# CAN_BUS_FOR_STM32.net
KiCad netlist of a schematic drawn in Altium Designer
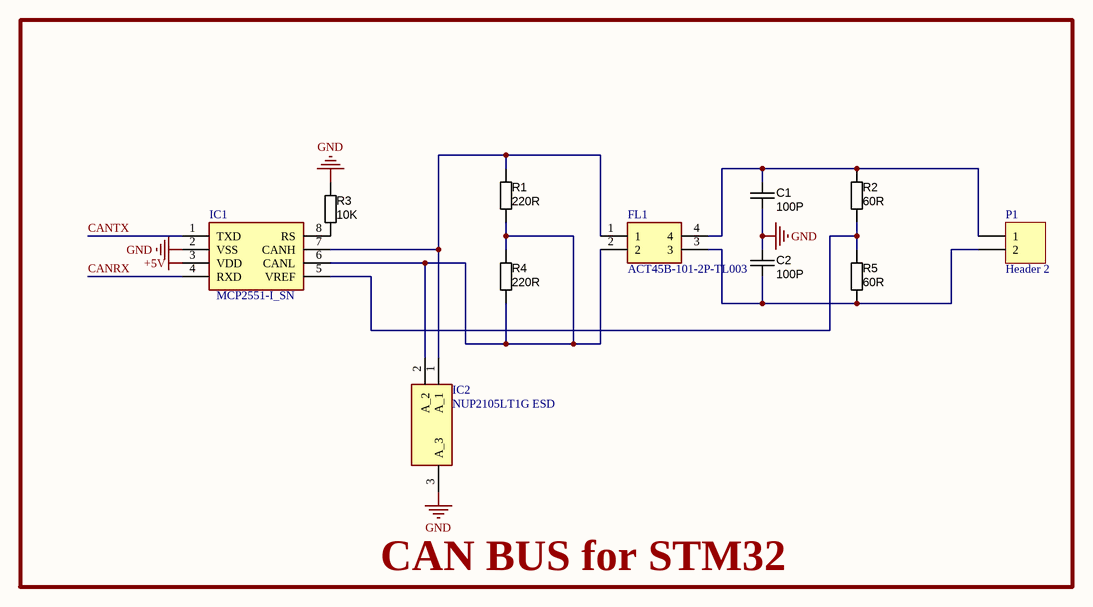
[diagram p0: CAN BUS FOR STM32.SchDoc]

(export (version "E")
  (design (tool "Eeschema 10.0.6"))
  (components
    (comp (ref "C1")
      (value "100P")
      (footprint "CAPC2012X135N")
      (description "Capacitor SMD Cer 100pF 10% 100V X7R 0805")
      (fields (field (name "TOLERANCE") "±10%") (field (name "Comment") "approved sub OK"))
      (libsource (lib "PBL - Capacitors") (part "CAPC_100n_0805_X7R_100V_10%"))
    )
    (comp (ref "C2")
      (value "100P")
      (footprint "CAPC2012X135N")
      (description "Capacitor SMD Cer 100pF 10% 100V X7R 0805")
      (fields (field (name "TOLERANCE") "±10%") (field (name "Comment") "approved sub OK"))
      (libsource (lib "PBL - Capacitors") (part "CAPC_100n_0805_X7R_100V_10%"))
    )
    (comp (ref "FL1")
      (value "ACT45B-101-2P-TL003")
      (footprint "SamacSys:ACT45B1012PTL003")
      (description "Filter")
      (fields (field (name "MOUSER PART NUMBER") "810-ACT45B1012PTL003"))
      (libsource (lib "*") (part "ACT45B-101-2P-TL003"))
    )
    (comp (ref "IC1")
      (value "MCP2551-I_SN")
      (footprint "SamacSys:SOIC127P600X175-8N")
      (description "Integrated Circuit")
      (fields
        (field (name "MANUFACTURER_PART_NUMBER") "MCP2551-I/SN")
        (field (name "MOUSER PART NUMBER") "579-MCP2551-I/SN")
      )
      (libsource (lib "*") (part "MCP2551-I_SN"))
    )
    (comp (ref "IC2")
      (value "NUP2105LT1G ESD")
      (footprint "SamacSys:SOT96P237X111-3N")
      (description "Integrated Circuit")
      (fields
        (field (name "MANUFACTURER_PART_NUMBER") "NUP2105LT1G")
        (field (name "MOUSER PART NUMBER") "863-NUP2105LT1G")
      )
      (libsource (lib "*") (part "NUP2105LT1G"))
    )
    (comp (ref "P1")
      (value "Header 2")
      (footprint "Terminal kf128 2pin 5.0")
      (description "Header, 2-Pin")
      (fields (field (name "PUBLISHER") "Altium Limited"))
      (libsource (lib "Miscellaneous Connectors") (part "Header 2"))
    )
    (comp (ref "R1")
      (value "220R")
      (footprint "RESC2012N_ZERO")
      (description "Resistor SMD chip 220 Ohm 0.125W 0805")
      (fields (field (name "Comment") "Jumper"))
      (libsource (lib "PBL - Resistors") (part "RES_0R_0805"))
    )
    (comp (ref "R2")
      (value "60R")
      (footprint "RESC2012N_ZERO")
      (description "Resistor SMD chip 60 Ohm 0.125W 0805")
      (fields (field (name "Comment") "Jumper"))
      (libsource (lib "PBL - Resistors") (part "RES_0R_0805"))
    )
    (comp (ref "R3")
      (value "10K")
      (footprint "RESC2012N_ZERO")
      (description "Resistor SMD chip 10KOhm 0.125W 0805")
      (fields (field (name "Comment") "Jumper"))
      (libsource (lib "PBL - Resistors") (part "RES_0R_0805"))
    )
    (comp (ref "R4")
      (value "220R")
      (footprint "RESC2012N_ZERO")
      (description "Resistor SMD chip 220 Ohm 0.125W 0805")
      (fields (field (name "Comment") "Jumper"))
      (libsource (lib "PBL - Resistors") (part "RES_0R_0805"))
    )
    (comp (ref "R5")
      (value "60R")
      (footprint "RESC2012N_ZERO")
      (description "Resistor SMD chip 60 Ohm 0.125W 0805")
      (fields (field (name "Comment") "Jumper"))
      (libsource (lib "PBL - Resistors") (part "RES_0R_0805"))
    )
  )
  (nets
    (net (code "1") (name "+5V") (class "Default")
      (node (ref "IC1") (pin "3") (pinfunction "VDD_3") (pintype "passive"))
    )
    (net (code "2") (name "/CANRX") (class "Default")
      (node (ref "IC1") (pin "4") (pinfunction "RXD_4") (pintype "passive"))
    )
    (net (code "3") (name "/CANTX") (class "Default")
      (node (ref "IC1") (pin "1") (pinfunction "TXD_1") (pintype "passive"))
    )
    (net (code "4") (name "GND") (class "Default")
      (node (ref "C1") (pin "2") (pintype "passive"))
      (node (ref "C2") (pin "1") (pintype "passive"))
      (node (ref "IC1") (pin "2") (pinfunction "VSS_2") (pintype "passive"))
      (node (ref "IC2") (pin "3") (pinfunction "A_3_3") (pintype "passive"))
      (node (ref "R3") (pin "1") (pinfunction "1_1") (pintype "passive"))
    )
    (net (code "5") (name "Net-(C1-Pad1)") (class "Default")
      (node (ref "C1") (pin "1") (pintype "passive"))
      (node (ref "FL1") (pin "4") (pinfunction "4_4") (pintype "passive"))
      (node (ref "P1") (pin "1") (pinfunction "1_1") (pintype "passive"))
      (node (ref "R2") (pin "1") (pinfunction "1_1") (pintype "passive"))
    )
    (net (code "6") (name "Net-(C2-Pad2)") (class "Default")
      (node (ref "C2") (pin "2") (pintype "passive"))
      (node (ref "FL1") (pin "3") (pinfunction "3_3") (pintype "passive"))
      (node (ref "P1") (pin "2") (pinfunction "2_2") (pintype "passive"))
      (node (ref "R5") (pin "2") (pinfunction "2_2") (pintype "passive"))
    )
    (net (code "7") (name "Net-(IC1-CANH)") (class "Default")
      (node (ref "FL1") (pin "1") (pinfunction "1_1") (pintype "passive"))
      (node (ref "IC1") (pin "7") (pinfunction "CANH_7") (pintype "passive"))
      (node (ref "IC2") (pin "1") (pinfunction "A_1_1") (pintype "passive"))
      (node (ref "R1") (pin "1") (pinfunction "1_1") (pintype "passive"))
    )
    (net (code "8") (name "Net-(IC1-CANL)") (class "Default")
      (node (ref "FL1") (pin "2") (pinfunction "2_2") (pintype "passive"))
      (node (ref "IC1") (pin "6") (pinfunction "CANL_6") (pintype "passive"))
      (node (ref "IC2") (pin "2") (pinfunction "A_2_2") (pintype "passive"))
      (node (ref "R1") (pin "2") (pinfunction "2_2") (pintype "passive"))
      (node (ref "R4") (pin "1") (pinfunction "1_1") (pintype "passive"))
      (node (ref "R4") (pin "2") (pinfunction "2_2") (pintype "passive"))
    )
    (net (code "9") (name "Net-(IC1-RS)") (class "Default")
      (node (ref "IC1") (pin "8") (pinfunction "RS_8") (pintype "passive"))
      (node (ref "R3") (pin "2") (pinfunction "2_2") (pintype "passive"))
    )
    (net (code "10") (name "Net-(IC1-VREF)") (class "Default")
      (node (ref "IC1") (pin "5") (pinfunction "VREF_5") (pintype "passive"))
      (node (ref "R2") (pin "2") (pinfunction "2_2") (pintype "passive"))
      (node (ref "R5") (pin "1") (pinfunction "1_1") (pintype "passive"))
    )
  )
)
